# RP2040_MCU.net
KiCad netlist of a schematic drawn in Altium Designer
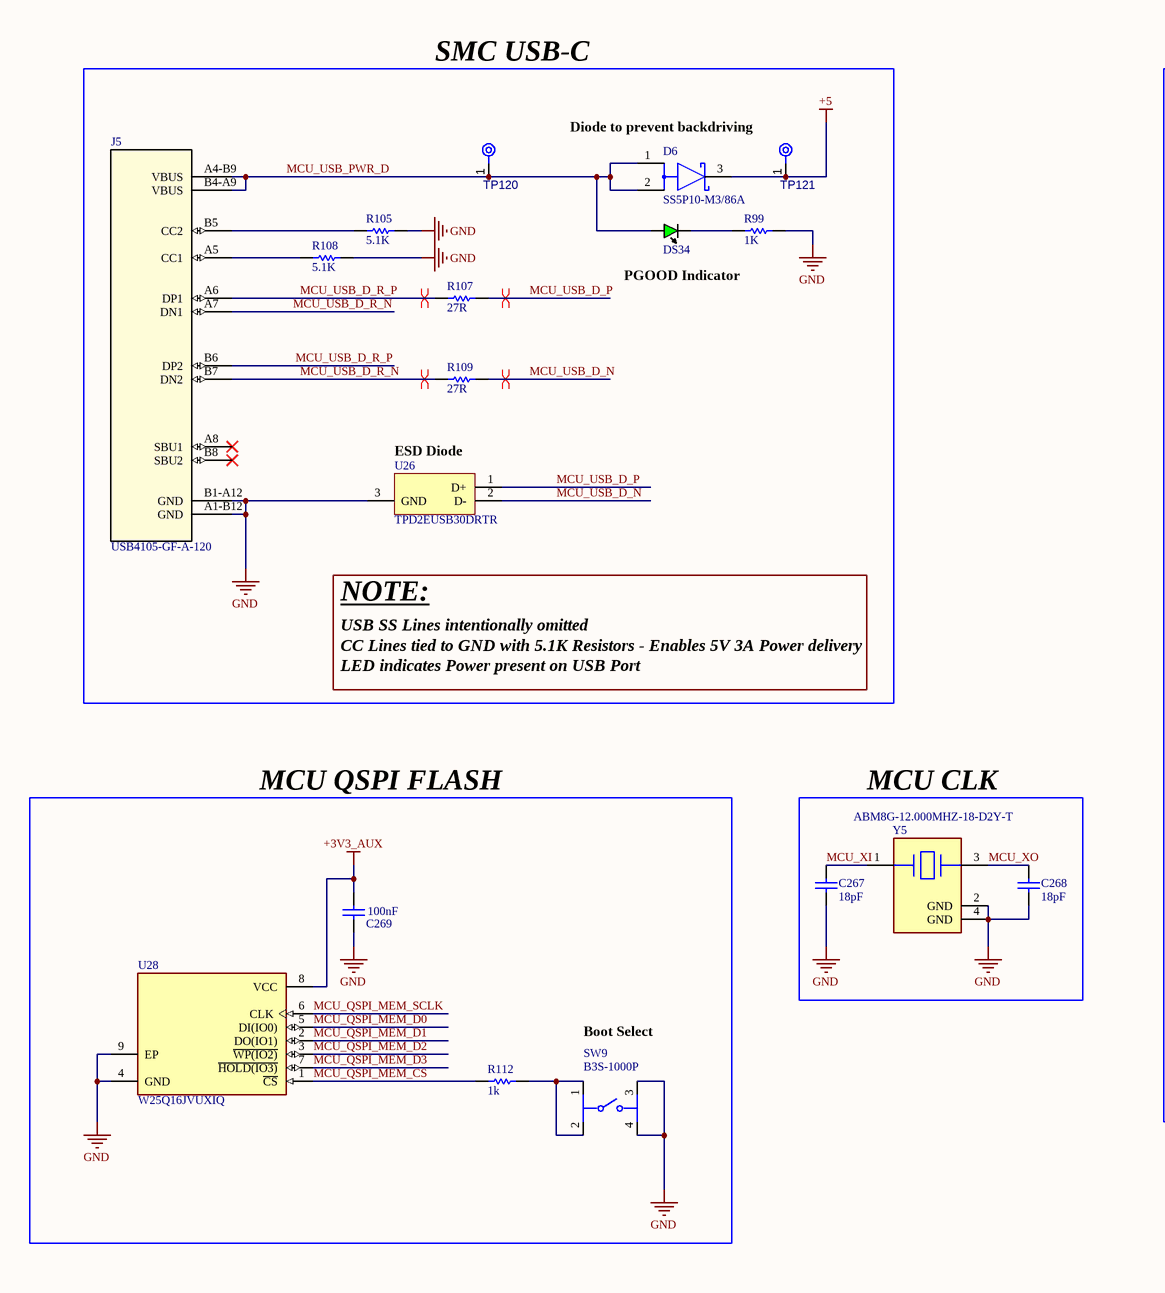
[diagram p0: RP2040 MCU.SchDoc, left]
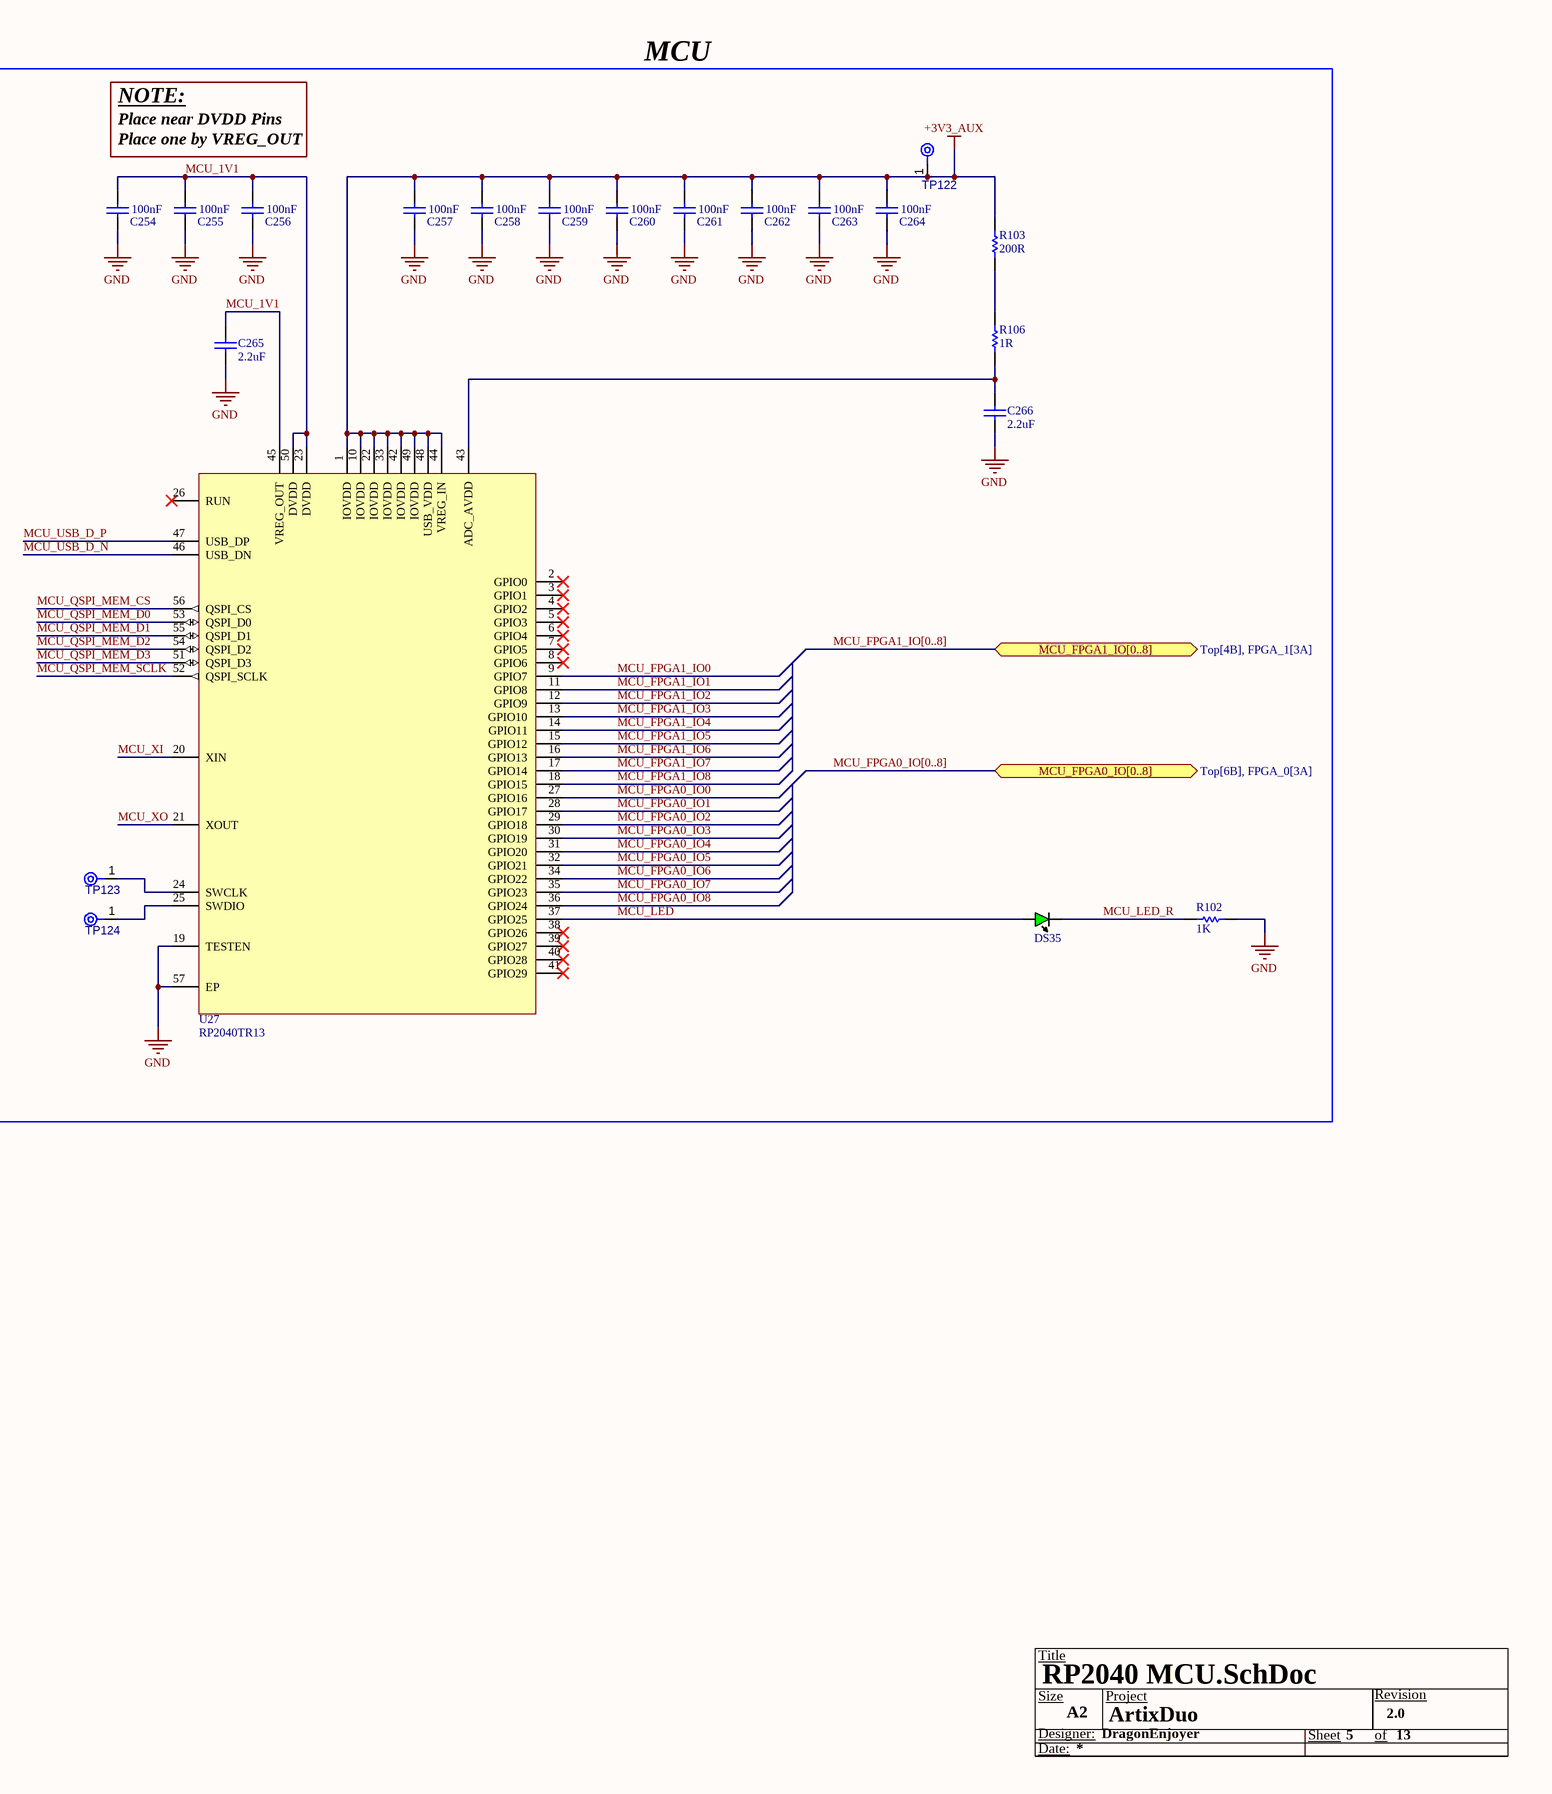
[diagram p1: RP2040 MCU.SchDoc, right]

(export (version "E")
  (design (tool "Eeschema 10.0.6"))
  (components
    (comp (ref "C254")
      (value "100nF")
      (footprint "CAPC1005X05N")
      (description "Cap Ceramic 0.1uF 50V X7R 20% SMD 0402 125°C Paper T/R GRM155R71H104ME14J")
      (fields (field (name "VOLTAGE") "50V"))
      (libsource (lib "Main Workspace") (part "CAP"))
    )
    (comp (ref "C255")
      (value "100nF")
      (footprint "CAPC1005X05N")
      (description "Cap Ceramic 0.1uF 50V X7R 20% SMD 0402 125°C Paper T/R GRM155R71H104ME14J")
      (fields (field (name "VOLTAGE") "50V"))
      (libsource (lib "Main Workspace") (part "CAP"))
    )
    (comp (ref "C256")
      (value "100nF")
      (footprint "CAPC1005X05N")
      (description "Cap Ceramic 0.1uF 50V X7R 20% SMD 0402 125°C Paper T/R GRM155R71H104ME14J")
      (fields (field (name "VOLTAGE") "50V"))
      (libsource (lib "Main Workspace") (part "CAP"))
    )
    (comp (ref "C257")
      (value "100nF")
      (footprint "CAPC1005X05N")
      (description "Cap Ceramic 0.1uF 50V X7R 20% SMD 0402 125°C Paper T/R GRM155R71H104ME14J")
      (fields (field (name "VOLTAGE") "50V"))
      (libsource (lib "Main Workspace") (part "CAP"))
    )
    (comp (ref "C258")
      (value "100nF")
      (footprint "CAPC1005X05N")
      (description "Cap Ceramic 0.1uF 50V X7R 20% SMD 0402 125°C Paper T/R GRM155R71H104ME14J")
      (fields (field (name "VOLTAGE") "50V"))
      (libsource (lib "Main Workspace") (part "CAP"))
    )
    (comp (ref "C259")
      (value "100nF")
      (footprint "CAPC1005X05N")
      (description "Cap Ceramic 0.1uF 50V X7R 20% SMD 0402 125°C Paper T/R GRM155R71H104ME14J")
      (fields (field (name "VOLTAGE") "50V"))
      (libsource (lib "Main Workspace") (part "CAP"))
    )
    (comp (ref "C260")
      (value "100nF")
      (footprint "CAPC1005X05N")
      (description "Cap Ceramic 0.1uF 50V X7R 20% SMD 0402 125°C Paper T/R GRM155R71H104ME14J")
      (fields (field (name "VOLTAGE") "50V"))
      (libsource (lib "Main Workspace") (part "CAP"))
    )
    (comp (ref "C261")
      (value "100nF")
      (footprint "CAPC1005X05N")
      (description "Cap Ceramic 0.1uF 50V X7R 20% SMD 0402 125°C Paper T/R GRM155R71H104ME14J")
      (fields (field (name "VOLTAGE") "50V"))
      (libsource (lib "Main Workspace") (part "CAP"))
    )
    (comp (ref "C262")
      (value "100nF")
      (footprint "CAPC1005X05N")
      (description "Cap Ceramic 0.1uF 50V X7R 20% SMD 0402 125°C Paper T/R GRM155R71H104ME14J")
      (fields (field (name "VOLTAGE") "50V"))
      (libsource (lib "Main Workspace") (part "CAP"))
    )
    (comp (ref "C263")
      (value "100nF")
      (footprint "CAPC1005X05N")
      (description "Cap Ceramic 0.1uF 50V X7R 20% SMD 0402 125°C Paper T/R GRM155R71H104ME14J")
      (fields (field (name "VOLTAGE") "50V"))
      (libsource (lib "Main Workspace") (part "CAP"))
    )
    (comp (ref "C264")
      (value "100nF")
      (footprint "CAPC1005X05N")
      (description "Cap Ceramic 0.1uF 50V X7R 20% SMD 0402 125°C Paper T/R GRM155R71H104ME14J")
      (fields (field (name "VOLTAGE") "50V"))
      (libsource (lib "Main Workspace") (part "CAP"))
    )
    (comp (ref "C265")
      (value "2.2uF")
      (footprint "CAPC1005X55X25NL05T10")
      (description "GRM155R60J225ME15D")
      (fields (field (name "MANUFACTURER") "Murata"))
      (libsource (lib "Altium Content Vault") (part "CAP"))
    )
    (comp (ref "C266")
      (value "2.2uF")
      (footprint "CAPC1005X55X25NL05T10")
      (description "GRM155R60J225ME15D")
      (fields (field (name "MANUFACTURER") "Murata"))
      (libsource (lib "Altium Content Vault") (part "CAP"))
    )
    (comp (ref "C267")
      (value "18pF")
      (footprint "CAPC1005X55X25LL05T10")
      (fields (field (name "MANUFACTURER") "Murata") (field (name "TOLERANCE") "±5%"))
      (libsource (lib "Altium Content Vault") (part "CAP-NP-2"))
    )
    (comp (ref "C268")
      (value "18pF")
      (footprint "CAPC1005X55X25LL05T10")
      (fields (field (name "MANUFACTURER") "Murata") (field (name "TOLERANCE") "±5%"))
      (libsource (lib "Altium Content Vault") (part "CAP-NP-2"))
    )
    (comp (ref "C269")
      (value "100nF")
      (footprint "CAPC1005X05N")
      (description "Cap Ceramic 0.1uF 50V X7R 20% SMD 0402 125°C Paper T/R GRM155R71H104ME14J")
      (fields (field (name "VOLTAGE") "50V"))
      (libsource (lib "Main Workspace") (part "CAP"))
    )
    (comp (ref "D6")
      (value "SS5P10-M3/86A")
      (footprint "FP-95570-MFG")
      (description "DIODE SCHOTTKY 100V 5A TO277A")
      (libsource (lib "Altium Content Vault") (part "03725f8997c85b601c823eea96032f8"))
    )
    (comp (ref "DS34")
      (value "SMLLX0603GWTR")
      (footprint "LUMX-SML-LX0603_V")
      (description "LED GREEN DIFFUSED SMD")
      (libsource (lib "Main Workspace") (part "LED-GREEN-AK-2"))
    )
    (comp (ref "DS35")
      (value "SMLLX0603GWTR")
      (footprint "LUMX-SML-LX0603_V")
      (description "LED GREEN DIFFUSED SMD")
      (libsource (lib "Main Workspace") (part "LED-GREEN-AK-2"))
    )
    (comp (ref "J5")
      (value "USB4105-GF-A-120")
      (footprint "USB4105-GF-A-120-Footprint-1")
      (libsource (lib "Main Workspace") (part "USB4105-GF-A-120"))
    )
    (comp (ref "R99")
      (value "1K")
      (footprint "RESC1005X40X25NL05T10")
      (description "CRCW04021K00FKEDHP")
      (fields (field (name "MANUFACTURER") "Vishay Dale"))
      (libsource (lib "Altium Content Vault") (part "RES"))
    )
    (comp (ref "R102")
      (value "1K")
      (footprint "RESC1005X40X25NL05T10")
      (description "CRCW04021K00FKEDHP")
      (fields (field (name "MANUFACTURER") "Vishay Dale"))
      (libsource (lib "Altium Content Vault") (part "RES"))
    )
    (comp (ref "R103")
      (value "200R")
      (footprint "RESC1005X40X25NL05T05")
      (description "CRCW0402200RJNED")
      (fields (field (name "MANUFACTURER") "Vishay Dale"))
      (libsource (lib "Altium Content Vault") (part "RES"))
    )
    (comp (ref "R105")
      (value "5.1K")
      (footprint "RESC1005X40X25NL05T10")
      (description "RC0402FR-075K1L")
      (fields (field (name "MANUFACTURER") "Yageo / Phycomp"))
      (libsource (lib "Altium Content Vault") (part "RES"))
    )
    (comp (ref "R106")
      (value "1R")
      (footprint "RESC1005X40X25NL05T05")
      (description "CRCW04021R00FKED")
      (fields (field (name "MANUFACTURER") "Vishay Dale"))
      (libsource (lib "Altium Content Vault") (part "RES"))
    )
    (comp (ref "R107")
      (value "27R")
      (footprint "RESC1005X40X25NL05T10")
      (description "RC0402JR-0727RL")
      (fields (field (name "MANUFACTURER") "Yageo / Phycomp"))
      (libsource (lib "Altium Content Vault") (part "RES"))
    )
    (comp (ref "R108")
      (value "5.1K")
      (footprint "RESC1005X40X25NL05T10")
      (description "RC0402FR-075K1L")
      (fields (field (name "MANUFACTURER") "Yageo / Phycomp"))
      (libsource (lib "Altium Content Vault") (part "RES"))
    )
    (comp (ref "R109")
      (value "27R")
      (footprint "RESC1005X40X25NL05T10")
      (description "RC0402JR-0727RL")
      (fields (field (name "MANUFACTURER") "Yageo / Phycomp"))
      (libsource (lib "Altium Content Vault") (part "RES"))
    )
    (comp (ref "R112")
      (value "1k")
      (footprint "RESC1005X40X25ML05T05")
      (description "Chip Resistor, 1 KOhm, +/- 1%, 0.1 W, -55 to 155 degC, 0402 (1005 Metric)")
      (fields (field (name "POWER") "100mW") (field (name "TOLERANCE") "1%"))
      (libsource (lib "Main Workspace") (part "RES-2"))
    )
    (comp (ref "SW9")
      (value "B3S-1000P")
      (footprint "FP-B3S-1000P-MFG")
      (description "SWITCH TACTILE SPST-NO 0.05A 24V")
      (libsource (lib "Altium Content Vault") (part "b8895f3f4cefb76e1819d2863dba89b"))
    )
    (comp (ref "TP120")
      (value "TPAD6R")
      (footprint "TP06R")
      (description "0.6mm round")
      (libsource (lib "Main Workspace") (part "CMP-001-0001-4"))
    )
    (comp (ref "TP121")
      (value "TPAD6R")
      (footprint "TP06R")
      (description "0.6mm round")
      (libsource (lib "Main Workspace") (part "CMP-001-0001-4"))
    )
    (comp (ref "TP122")
      (value "TPAD6R")
      (footprint "TP06R")
      (description "0.6mm round")
      (libsource (lib "Main Workspace") (part "CMP-001-0001-4"))
    )
    (comp (ref "TP123")
      (value "TPAD6R")
      (footprint "TP06R")
      (description "0.6mm round")
      (libsource (lib "Main Workspace") (part "CMP-001-0001-4"))
    )
    (comp (ref "TP124")
      (value "TPAD6R")
      (footprint "TP06R")
      (description "0.6mm round")
      (libsource (lib "Main Workspace") (part "CMP-001-0001-4"))
    )
    (comp (ref "U26")
      (value "TPD2EUSB30DRTR")
      (footprint "DRT0003A")
      (fields (field (name "MANUFACTURER") "Texas Instruments"))
      (libsource (lib "Altium Content Vault") (part "TI-TPD2EUSB30-SOT_DRT-3"))
    )
    (comp (ref "U27")
      (value "RP2040TR13")
      (footprint "QFN40P700X700X80_HS-57N")
      (description "Mcu, 32 Bit, 133MHZ, QFN-56;")
      (libsource (lib "Main Workspace") (part "RP2040"))
    )
    (comp (ref "U28")
      (value "W25Q16JVUXIQ")
      (footprint "FP-UX-MFG")
      (description "IC FLASH 16MBIT SPI/QUAD 8USON")
      (libsource (lib "Altium Content Vault") (part "ef7e6bbff5b18f94b0c5acc221a373e"))
    )
    (comp (ref "Y5")
      (value "ABM8G-12.000MHZ-18-D2Y-T")
      (footprint "FP-ABM8G-MFG")
      (description "Crystal 12MHz ±20ppm (Tol) ±30ppm (Stability) 18pF FUND 120Ω 4-Pin SMD T/R")
      (fields (field (name "TOLERANCE") "20ppm"))
      (libsource (lib "Altium Content Vault") (part "48e526d86b7f2615d98721063c72f49"))
    )
  )
  (nets
    (net (code "1") (name "+3V3_AUX") (class "Default")
      (node (ref "C257") (pin "2") (pinfunction "2_2") (pintype "passive"))
      (node (ref "C258") (pin "2") (pinfunction "2_2") (pintype "passive"))
      (node (ref "C259") (pin "2") (pinfunction "2_2") (pintype "passive"))
      (node (ref "C260") (pin "2") (pinfunction "2_2") (pintype "passive"))
      (node (ref "C261") (pin "2") (pinfunction "2_2") (pintype "passive"))
      (node (ref "C262") (pin "2") (pinfunction "2_2") (pintype "passive"))
      (node (ref "C263") (pin "2") (pinfunction "2_2") (pintype "passive"))
      (node (ref "C264") (pin "2") (pinfunction "2_2") (pintype "passive"))
      (node (ref "C269") (pin "2") (pinfunction "2_2") (pintype "passive"))
      (node (ref "R103") (pin "2") (pinfunction "2_2") (pintype "passive"))
      (node (ref "TP122") (pin "1") (pinfunction "TP_1") (pintype "passive"))
      (node (ref "U27") (pin "1") (pinfunction "IOVDD_1") (pintype "passive"))
      (node (ref "U27") (pin "10") (pinfunction "IOVDD_10") (pintype "passive"))
      (node (ref "U27") (pin "22") (pinfunction "IOVDD_22") (pintype "passive"))
      (node (ref "U27") (pin "33") (pinfunction "IOVDD_33") (pintype "passive"))
      (node (ref "U27") (pin "42") (pinfunction "IOVDD_42") (pintype "passive"))
      (node (ref "U27") (pin "44") (pinfunction "VREG_IN_44") (pintype "passive"))
      (node (ref "U27") (pin "48") (pinfunction "USB_VDD_48") (pintype "passive"))
      (node (ref "U27") (pin "49") (pinfunction "IOVDD_49") (pintype "passive"))
      (node (ref "U28") (pin "8") (pinfunction "VCC_8") (pintype "power_in"))
    )
    (net (code "2") (name "+5") (class "Default")
      (node (ref "D6") (pin "3") (pinfunction "C_3") (pintype "passive"))
      (node (ref "TP121") (pin "1") (pinfunction "TP_1") (pintype "passive"))
    )
    (net (code "4") (name "/MCU_1V1") (class "Default")
      (node (ref "C254") (pin "2") (pinfunction "2_2") (pintype "passive"))
      (node (ref "C255") (pin "2") (pinfunction "2_2") (pintype "passive"))
      (node (ref "C256") (pin "2") (pinfunction "2_2") (pintype "passive"))
      (node (ref "C265") (pin "2") (pinfunction "2_2") (pintype "passive"))
      (node (ref "U27") (pin "23") (pinfunction "DVDD_23") (pintype "passive"))
      (node (ref "U27") (pin "45") (pinfunction "VREG_OUT_45") (pintype "passive"))
      (node (ref "U27") (pin "50") (pinfunction "DVDD_50") (pintype "passive"))
    )
    (net (code "5") (name "/MCU_FPGA0_IO0") (class "Default")
      (node (ref "U27") (pin "27") (pinfunction "GPIO16_27") (pintype "passive"))
    )
    (net (code "6") (name "/MCU_FPGA0_IO1") (class "Default")
      (node (ref "U27") (pin "28") (pinfunction "GPIO17_28") (pintype "passive"))
    )
    (net (code "7") (name "/MCU_FPGA0_IO2") (class "Default")
      (node (ref "U27") (pin "29") (pinfunction "GPIO18_29") (pintype "passive"))
    )
    (net (code "8") (name "/MCU_FPGA0_IO3") (class "Default")
      (node (ref "U27") (pin "30") (pinfunction "GPIO19_30") (pintype "passive"))
    )
    (net (code "9") (name "/MCU_FPGA0_IO4") (class "Default")
      (node (ref "U27") (pin "31") (pinfunction "GPIO20_31") (pintype "passive"))
    )
    (net (code "10") (name "/MCU_FPGA0_IO5") (class "Default")
      (node (ref "U27") (pin "32") (pinfunction "GPIO21_32") (pintype "passive"))
    )
    (net (code "11") (name "/MCU_FPGA0_IO6") (class "Default")
      (node (ref "U27") (pin "34") (pinfunction "GPIO22_34") (pintype "passive"))
    )
    (net (code "12") (name "/MCU_FPGA0_IO7") (class "Default")
      (node (ref "U27") (pin "35") (pinfunction "GPIO23_35") (pintype "passive"))
    )
    (net (code "13") (name "/MCU_FPGA0_IO8") (class "Default")
      (node (ref "U27") (pin "36") (pinfunction "GPIO24_36") (pintype "passive"))
    )
    (net (code "15") (name "/MCU_FPGA1_IO0") (class "Default")
      (node (ref "U27") (pin "9") (pinfunction "GPIO7_9") (pintype "passive"))
    )
    (net (code "16") (name "/MCU_FPGA1_IO1") (class "Default")
      (node (ref "U27") (pin "11") (pinfunction "GPIO8_11") (pintype "passive"))
    )
    (net (code "17") (name "/MCU_FPGA1_IO2") (class "Default")
      (node (ref "U27") (pin "12") (pinfunction "GPIO9_12") (pintype "passive"))
    )
    (net (code "18") (name "/MCU_FPGA1_IO3") (class "Default")
      (node (ref "U27") (pin "13") (pinfunction "GPIO10_13") (pintype "passive"))
    )
    (net (code "19") (name "/MCU_FPGA1_IO4") (class "Default")
      (node (ref "U27") (pin "14") (pinfunction "GPIO11_14") (pintype "passive"))
    )
    (net (code "20") (name "/MCU_FPGA1_IO5") (class "Default")
      (node (ref "U27") (pin "15") (pinfunction "GPIO12_15") (pintype "passive"))
    )
    (net (code "21") (name "/MCU_FPGA1_IO6") (class "Default")
      (node (ref "U27") (pin "16") (pinfunction "GPIO13_16") (pintype "passive"))
    )
    (net (code "22") (name "/MCU_FPGA1_IO7") (class "Default")
      (node (ref "U27") (pin "17") (pinfunction "GPIO14_17") (pintype "passive"))
    )
    (net (code "23") (name "/MCU_FPGA1_IO8") (class "Default")
      (node (ref "U27") (pin "18") (pinfunction "GPIO15_18") (pintype "passive"))
    )
    (net (code "25") (name "/MCU_LED") (class "Default")
      (node (ref "DS35") (pin "1") (pinfunction "A_1") (pintype "passive"))
      (node (ref "U27") (pin "37") (pinfunction "GPIO25_37") (pintype "passive"))
    )
    (net (code "26") (name "/MCU_LED_R") (class "Default")
      (node (ref "DS35") (pin "2") (pinfunction "K_2") (pintype "passive"))
      (node (ref "R102") (pin "2") (pinfunction "2_2") (pintype "passive"))
    )
    (net (code "27") (name "/MCU_QSPI_MEM_CS") (class "Default")
      (node (ref "R112") (pin "1") (pinfunction "1_1") (pintype "passive"))
      (node (ref "U27") (pin "56") (pinfunction "QSPI_CS_56") (pintype "output"))
      (node (ref "U28") (pin "1") (pinfunction "~{CS}_1") (pintype "input"))
    )
    (net (code "28") (name "/MCU_QSPI_MEM_D0") (class "Default")
      (node (ref "U27") (pin "53") (pinfunction "QSPI_D0_53") (pintype "bidirectional"))
      (node (ref "U28") (pin "5") (pinfunction "DI(IO0)_5") (pintype "bidirectional"))
    )
    (net (code "29") (name "/MCU_QSPI_MEM_D1") (class "Default")
      (node (ref "U27") (pin "55") (pinfunction "QSPI_D1_55") (pintype "bidirectional"))
      (node (ref "U28") (pin "2") (pinfunction "DO(IO1)_2") (pintype "bidirectional"))
    )
    (net (code "30") (name "/MCU_QSPI_MEM_D2") (class "Default")
      (node (ref "U27") (pin "54") (pinfunction "QSPI_D2_54") (pintype "bidirectional"))
      (node (ref "U28") (pin "3") (pinfunction "~{WP(IO2)}_3") (pintype "bidirectional"))
    )
    (net (code "31") (name "/MCU_QSPI_MEM_D3") (class "Default")
      (node (ref "U27") (pin "51") (pinfunction "QSPI_D3_51") (pintype "bidirectional"))
      (node (ref "U28") (pin "7") (pinfunction "~{HOLD(IO3)}_7") (pintype "bidirectional"))
    )
    (net (code "32") (name "/MCU_QSPI_MEM_SCLK") (class "Default")
      (node (ref "U27") (pin "52") (pinfunction "QSPI_SCLK_52") (pintype "output"))
      (node (ref "U28") (pin "6") (pinfunction "CLK_6") (pintype "input"))
    )
    (net (code "33") (name "/MCU_USB_D_N") (class "Default")
      (node (ref "R109") (pin "2") (pinfunction "2_2") (pintype "passive"))
      (node (ref "U26") (pin "2") (pinfunction "D-_2") (pintype "passive"))
      (node (ref "U27") (pin "46") (pinfunction "USB_DN_46") (pintype "passive"))
    )
    (net (code "34") (name "/MCU_USB_D_P") (class "Default")
      (node (ref "R107") (pin "2") (pinfunction "2_2") (pintype "passive"))
      (node (ref "U26") (pin "1") (pinfunction "D+_1") (pintype "passive"))
      (node (ref "U27") (pin "47") (pinfunction "USB_DP_47") (pintype "passive"))
    )
    (net (code "35") (name "/MCU_USB_D_R_N") (class "Default")
      (node (ref "J5") (pin "A7") (pinfunction "DN1_A7") (pintype "bidirectional"))
      (node (ref "J5") (pin "B7") (pinfunction "DN2_B7") (pintype "bidirectional"))
      (node (ref "R109") (pin "1") (pinfunction "1_1") (pintype "passive"))
    )
    (net (code "36") (name "/MCU_USB_D_R_P") (class "Default")
      (node (ref "J5") (pin "A6") (pinfunction "DP1_A6") (pintype "bidirectional"))
      (node (ref "J5") (pin "B6") (pinfunction "DP2_B6") (pintype "bidirectional"))
      (node (ref "R107") (pin "1") (pinfunction "1_1") (pintype "passive"))
    )
    (net (code "37") (name "/MCU_USB_PWR_D") (class "Default")
      (node (ref "D6") (pin "1") (pinfunction "A_1") (pintype "passive"))
      (node (ref "D6") (pin "2") (pinfunction "A_2") (pintype "passive"))
      (node (ref "DS34") (pin "1") (pinfunction "A_1") (pintype "passive"))
      (node (ref "J5") (pin "A4-B9") (pinfunction "VBUS_A4-B9") (pintype "power_in"))
      (node (ref "J5") (pin "B4-A9") (pinfunction "VBUS_B4-A9") (pintype "power_in"))
      (node (ref "TP120") (pin "1") (pinfunction "TP_1") (pintype "passive"))
    )
    (net (code "38") (name "/MCU_XI") (class "Default")
      (node (ref "C267") (pin "2") (pinfunction "2_2") (pintype "passive"))
      (node (ref "U27") (pin "20") (pinfunction "XIN_20") (pintype "passive"))
      (node (ref "Y5") (pin "1") (pinfunction "1_1") (pintype "passive"))
    )
    (net (code "39") (name "/MCU_XO") (class "Default")
      (node (ref "C268") (pin "2") (pinfunction "2_2") (pintype "passive"))
      (node (ref "U27") (pin "21") (pinfunction "XOUT_21") (pintype "passive"))
      (node (ref "Y5") (pin "3") (pinfunction "3_3") (pintype "passive"))
    )
    (net (code "40") (name "GND") (class "Default")
      (node (ref "C254") (pin "1") (pinfunction "1_1") (pintype "passive"))
      (node (ref "C255") (pin "1") (pinfunction "1_1") (pintype "passive"))
      (node (ref "C256") (pin "1") (pinfunction "1_1") (pintype "passive"))
      (node (ref "C257") (pin "1") (pinfunction "1_1") (pintype "passive"))
      (node (ref "C258") (pin "1") (pinfunction "1_1") (pintype "passive"))
      (node (ref "C259") (pin "1") (pinfunction "1_1") (pintype "passive"))
      (node (ref "C260") (pin "1") (pinfunction "1_1") (pintype "passive"))
      (node (ref "C261") (pin "1") (pinfunction "1_1") (pintype "passive"))
      (node (ref "C262") (pin "1") (pinfunction "1_1") (pintype "passive"))
      (node (ref "C263") (pin "1") (pinfunction "1_1") (pintype "passive"))
      (node (ref "C264") (pin "1") (pinfunction "1_1") (pintype "passive"))
      (node (ref "C265") (pin "1") (pinfunction "1_1") (pintype "passive"))
      (node (ref "C266") (pin "1") (pinfunction "1_1") (pintype "passive"))
      (node (ref "C267") (pin "1") (pinfunction "1_1") (pintype "passive"))
      (node (ref "C268") (pin "1") (pinfunction "1_1") (pintype "passive"))
      (node (ref "C269") (pin "1") (pinfunction "1_1") (pintype "passive"))
      (node (ref "J5") (pin "A1-B12") (pinfunction "GND_A1-B12") (pintype "power_in"))
      (node (ref "J5") (pin "B1-A12") (pinfunction "GND_B1-A12") (pintype "power_in"))
      (node (ref "R102") (pin "1") (pinfunction "1_1") (pintype "passive"))
      (node (ref "R105") (pin "2") (pinfunction "2_2") (pintype "passive"))
      (node (ref "R108") (pin "2") (pinfunction "2_2") (pintype "passive"))
      (node (ref "R99") (pin "1") (pinfunction "1_1") (pintype "passive"))
      (node (ref "SW9") (pin "3") (pinfunction "3_3") (pintype "passive"))
      (node (ref "SW9") (pin "4") (pinfunction "4_4") (pintype "passive"))
      (node (ref "U26") (pin "3") (pinfunction "GND_3") (pintype "power_in"))
      (node (ref "U27") (pin "19") (pinfunction "TESTEN_19") (pintype "passive"))
      (node (ref "U27") (pin "57") (pinfunction "EP_57") (pintype "passive"))
      (node (ref "U28") (pin "4") (pinfunction "GND_4") (pintype "power_in"))
      (node (ref "U28") (pin "9") (pinfunction "EP_9") (pintype "passive"))
      (node (ref "Y5") (pin "2") (pinfunction "GND_2") (pintype "power_in"))
      (node (ref "Y5") (pin "4") (pinfunction "GND_4") (pintype "power_in"))
    )
    (net (code "41") (name "Net-(DS34-K)") (class "Default")
      (node (ref "DS34") (pin "2") (pinfunction "K_2") (pintype "passive"))
      (node (ref "R99") (pin "2") (pinfunction "2_2") (pintype "passive"))
    )
    (net (code "42") (name "Net-(J5-CC1)") (class "Default")
      (node (ref "J5") (pin "A5") (pinfunction "CC1_A5") (pintype "bidirectional"))
      (node (ref "R108") (pin "1") (pinfunction "1_1") (pintype "passive"))
    )
    (net (code "43") (name "Net-(J5-CC2)") (class "Default")
      (node (ref "J5") (pin "B5") (pinfunction "CC2_B5") (pintype "bidirectional"))
      (node (ref "R105") (pin "1") (pinfunction "1_1") (pintype "passive"))
    )
    (net (code "44") (name "Net-(R103-Pad1)") (class "Default")
      (node (ref "R103") (pin "1") (pinfunction "1_1") (pintype "passive"))
      (node (ref "R106") (pin "2") (pinfunction "2_2") (pintype "passive"))
    )
    (net (code "45") (name "Net-(R112-Pad2)") (class "Default")
      (node (ref "R112") (pin "2") (pinfunction "2_2") (pintype "passive"))
      (node (ref "SW9") (pin "1") (pinfunction "1_1") (pintype "passive"))
      (node (ref "SW9") (pin "2") (pinfunction "2_2") (pintype "passive"))
    )
    (net (code "46") (name "Net-(TP123-TP)") (class "Default")
      (node (ref "TP123") (pin "1") (pinfunction "TP_1") (pintype "passive"))
      (node (ref "U27") (pin "24") (pinfunction "SWCLK_24") (pintype "passive"))
    )
    (net (code "47") (name "Net-(TP124-TP)") (class "Default")
      (node (ref "TP124") (pin "1") (pinfunction "TP_1") (pintype "passive"))
      (node (ref "U27") (pin "25") (pinfunction "SWDIO_25") (pintype "passive"))
    )
    (net (code "48") (name "Net-(U27-ADC_AVDD)") (class "Default")
      (node (ref "C266") (pin "2") (pinfunction "2_2") (pintype "passive"))
      (node (ref "R106") (pin "1") (pinfunction "1_1") (pintype "passive"))
      (node (ref "U27") (pin "43") (pinfunction "ADC_AVDD_43") (pintype "passive"))
    )
    (net (code "49") (name "unconnected-(J5-SBU1-PadA8)") (class "Default")
      (node (ref "J5") (pin "A8") (pinfunction "SBU1_A8") (pintype "bidirectional+no_connect"))
    )
    (net (code "50") (name "unconnected-(J5-SBU2-PadB8)") (class "Default")
      (node (ref "J5") (pin "B8") (pinfunction "SBU2_B8") (pintype "bidirectional+no_connect"))
    )
    (net (code "51") (name "unconnected-(U27-GPIO0-Pad2)") (class "Default")
      (node (ref "U27") (pin "2") (pinfunction "GPIO0_2") (pintype "passive+no_connect"))
    )
    (net (code "52") (name "unconnected-(U27-GPIO1-Pad3)") (class "Default")
      (node (ref "U27") (pin "3") (pinfunction "GPIO1_3") (pintype "passive+no_connect"))
    )
    (net (code "53") (name "unconnected-(U27-GPIO2-Pad4)") (class "Default")
      (node (ref "U27") (pin "4") (pinfunction "GPIO2_4") (pintype "passive+no_connect"))
    )
    (net (code "54") (name "unconnected-(U27-GPIO3-Pad5)") (class "Default")
      (node (ref "U27") (pin "5") (pinfunction "GPIO3_5") (pintype "passive+no_connect"))
    )
    (net (code "55") (name "unconnected-(U27-GPIO4-Pad6)") (class "Default")
      (node (ref "U27") (pin "6") (pinfunction "GPIO4_6") (pintype "passive+no_connect"))
    )
    (net (code "56") (name "unconnected-(U27-GPIO5-Pad7)") (class "Default")
      (node (ref "U27") (pin "7") (pinfunction "GPIO5_7") (pintype "passive+no_connect"))
    )
    (net (code "57") (name "unconnected-(U27-GPIO6-Pad8)") (class "Default")
      (node (ref "U27") (pin "8") (pinfunction "GPIO6_8") (pintype "passive+no_connect"))
    )
    (net (code "58") (name "unconnected-(U27-GPIO26-Pad38)") (class "Default")
      (node (ref "U27") (pin "38") (pinfunction "GPIO26_38") (pintype "passive+no_connect"))
    )
    (net (code "59") (name "unconnected-(U27-GPIO27-Pad39)") (class "Default")
      (node (ref "U27") (pin "39") (pinfunction "GPIO27_39") (pintype "passive+no_connect"))
    )
    (net (code "60") (name "unconnected-(U27-GPIO28-Pad40)") (class "Default")
      (node (ref "U27") (pin "40") (pinfunction "GPIO28_40") (pintype "passive+no_connect"))
    )
    (net (code "61") (name "unconnected-(U27-GPIO29-Pad41)") (class "Default")
      (node (ref "U27") (pin "41") (pinfunction "GPIO29_41") (pintype "passive+no_connect"))
    )
    (net (code "62") (name "unconnected-(U27-RUN-Pad26)") (class "Default")
      (node (ref "U27") (pin "26") (pinfunction "RUN_26") (pintype "passive+no_connect"))
    )
  )
)
